# AY_Soundcard.net
KiCad netlist of a schematic drawn in EAGLE
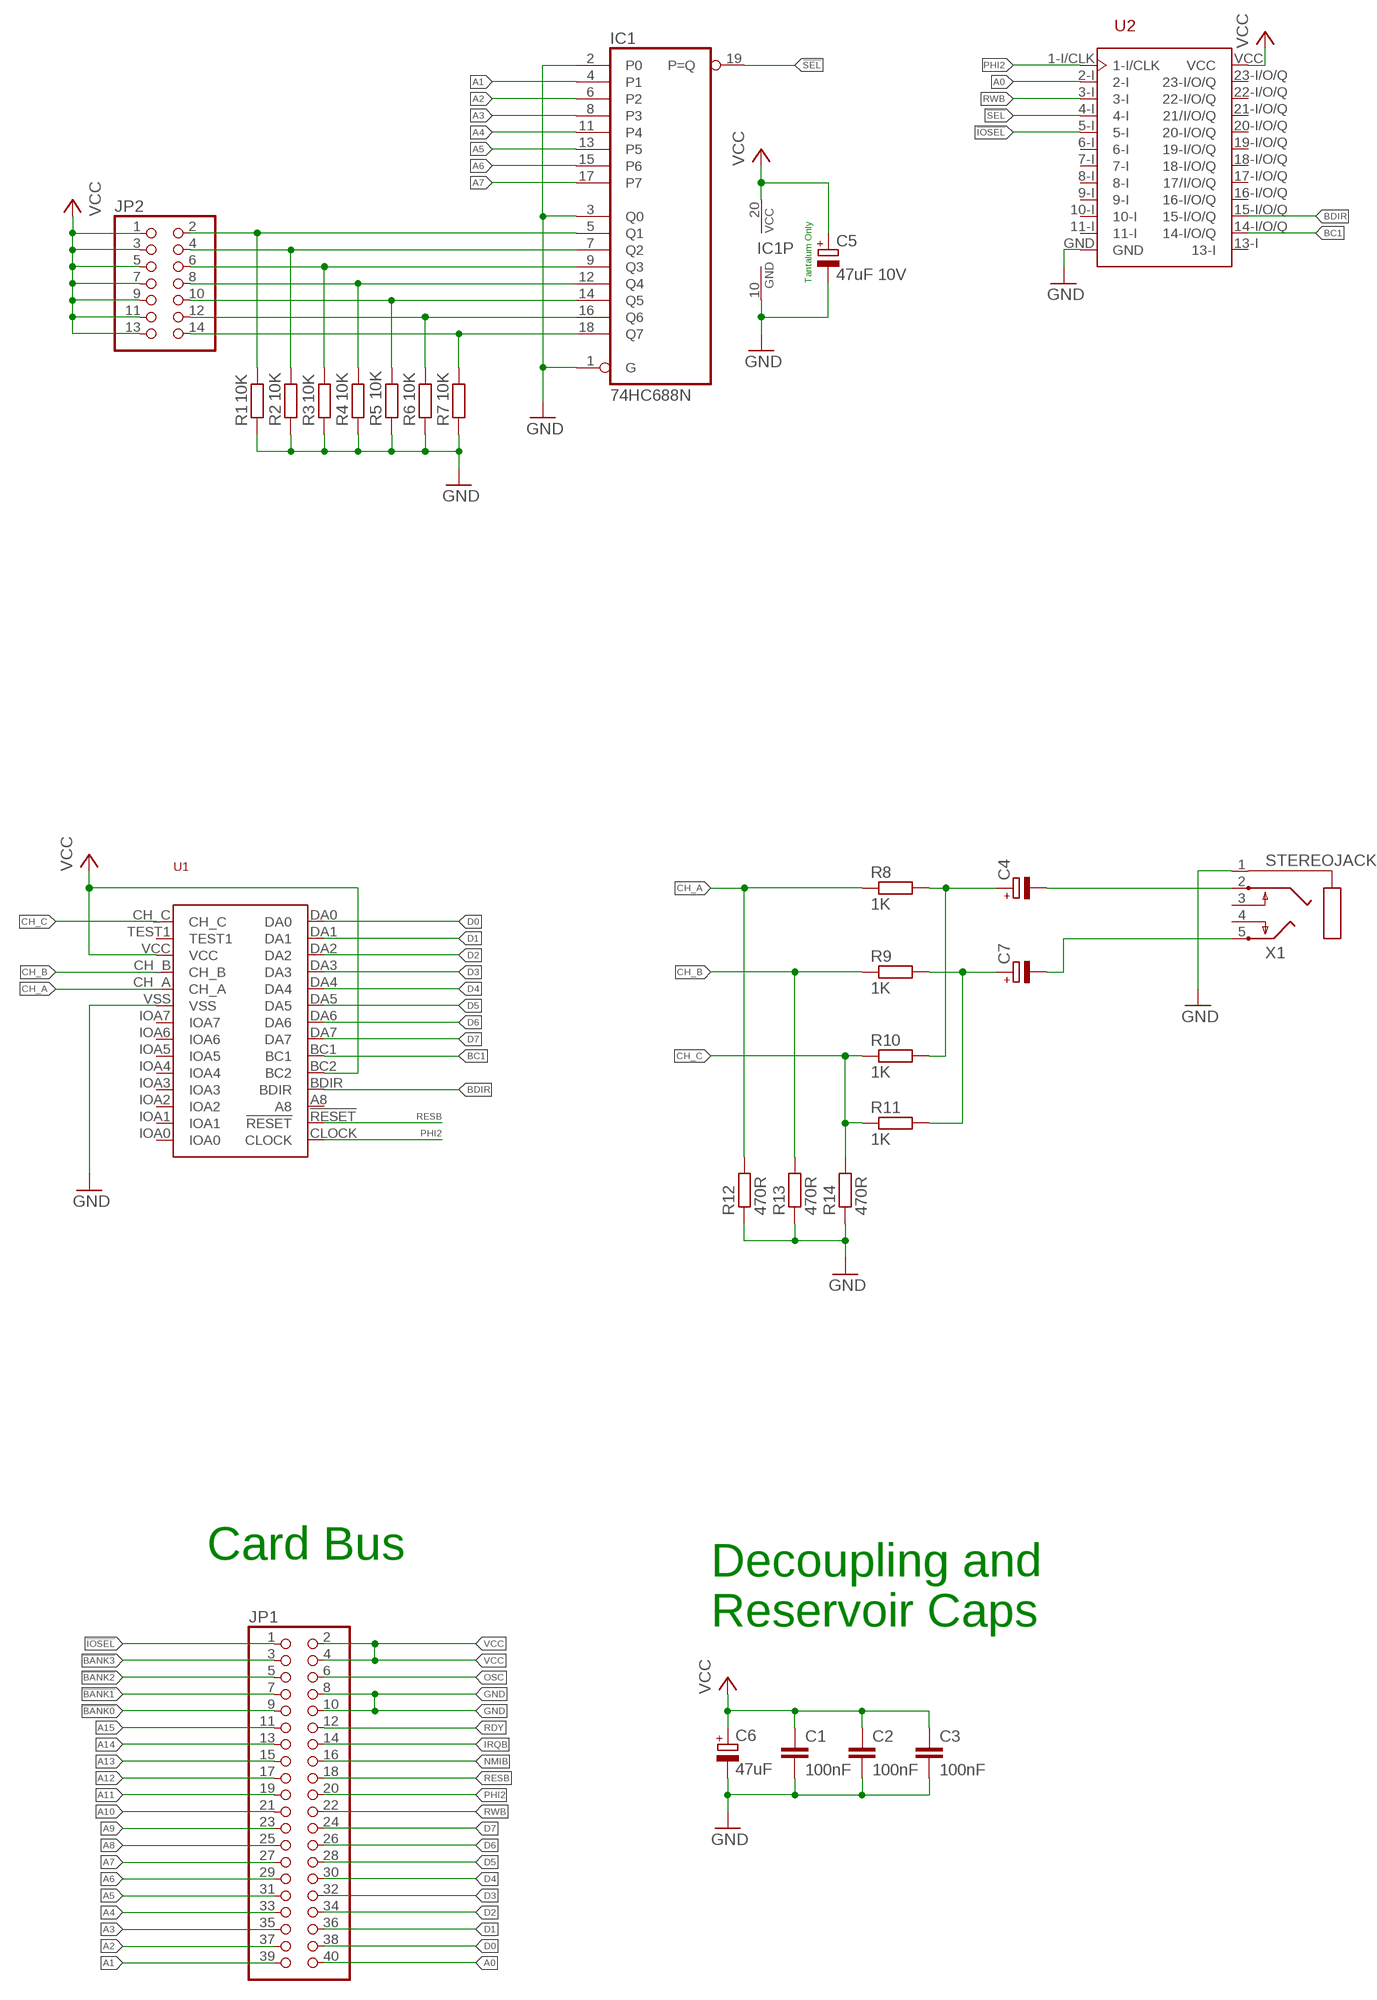
[diagram p0: schematic, sheet 1]

(export (version "E")
  (design (tool "Eeschema 10.0.6"))
  (components
    (comp (ref "C1")
      (value "100nF")
      (footprint "eagle-import:C050-025X075")
      (libsource (lib "eagle-import") (part "C-EU050-025X075"))
    )
    (comp (ref "C2")
      (value "100nF")
      (footprint "eagle-import:C050-025X075")
      (libsource (lib "eagle-import") (part "C-EU050-025X075"))
    )
    (comp (ref "C3")
      (value "100nF")
      (footprint "eagle-import:C050-025X075")
      (libsource (lib "eagle-import") (part "C-EU050-025X075"))
    )
    (comp (ref "C4")
      (value "CPOL-EUE2-5")
      (footprint "eagle-import:E2-5")
      (libsource (lib "eagle-import") (part "CPOL-EUE2-5"))
    )
    (comp (ref "C5")
      (value "47uF 10V")
      (footprint "eagle-import:E5-6")
      (libsource (lib "eagle-import") (part "CPOL-EUE5-6"))
    )
    (comp (ref "C6")
      (value "47uF")
      (footprint "eagle-import:E2,5-7")
      (libsource (lib "eagle-import") (part "CPOL-EUE2.5-7"))
    )
    (comp (ref "C7")
      (value "CPOL-EUE2-5")
      (footprint "eagle-import:E2-5")
      (libsource (lib "eagle-import") (part "CPOL-EUE2-5"))
    )
    (comp (ref "IC1")
      (value "74HC688N")
      (footprint "eagle-import:DIL20")
      (libsource (lib "eagle-import") (part "74688NHC"))
    )
    (comp (ref "JP1")
      (value "PINHD-2X20/90")
      (footprint "eagle-import:2X20_90")
      (libsource (lib "eagle-import") (part "PINHD-2X20/90"))
    )
    (comp (ref "JP2")
      (value "PINHD-2X7")
      (footprint "eagle-import:2X07")
      (libsource (lib "eagle-import") (part "PINHD-2X7"))
    )
    (comp (ref "R1")
      (value "10K")
      (footprint "eagle-import:0207_2V")
      (libsource (lib "eagle-import") (part "R-EU_0207/2V"))
    )
    (comp (ref "R2")
      (value "10K")
      (footprint "eagle-import:0207_2V")
      (libsource (lib "eagle-import") (part "R-EU_0207/2V"))
    )
    (comp (ref "R3")
      (value "10K")
      (footprint "eagle-import:0207_2V")
      (libsource (lib "eagle-import") (part "R-EU_0207/2V"))
    )
    (comp (ref "R4")
      (value "10K")
      (footprint "eagle-import:0207_2V")
      (libsource (lib "eagle-import") (part "R-EU_0207/2V"))
    )
    (comp (ref "R5")
      (value "10K")
      (footprint "eagle-import:0207_2V")
      (libsource (lib "eagle-import") (part "R-EU_0207/2V"))
    )
    (comp (ref "R6")
      (value "10K")
      (footprint "eagle-import:0207_2V")
      (libsource (lib "eagle-import") (part "R-EU_0207/2V"))
    )
    (comp (ref "R7")
      (value "10K")
      (footprint "eagle-import:0207_2V")
      (libsource (lib "eagle-import") (part "R-EU_0207/2V"))
    )
    (comp (ref "R8")
      (value "1K")
      (footprint "eagle-import:0207_2V")
      (libsource (lib "eagle-import") (part "R-EU_0207/2V"))
    )
    (comp (ref "R9")
      (value "1K")
      (footprint "eagle-import:0207_2V")
      (libsource (lib "eagle-import") (part "R-EU_0207/2V"))
    )
    (comp (ref "R10")
      (value "1K")
      (footprint "eagle-import:0207_2V")
      (libsource (lib "eagle-import") (part "R-EU_0207/2V"))
    )
    (comp (ref "R11")
      (value "1K")
      (footprint "eagle-import:0207_2V")
      (libsource (lib "eagle-import") (part "R-EU_0207/2V"))
    )
    (comp (ref "R12")
      (value "470R")
      (footprint "eagle-import:0207_2V")
      (libsource (lib "eagle-import") (part "R-EU_0207/2V"))
    )
    (comp (ref "R13")
      (value "470R")
      (footprint "eagle-import:0207_10")
      (libsource (lib "eagle-import") (part "R-EU_0207/10"))
    )
    (comp (ref "R14")
      (value "470R")
      (footprint "eagle-import:0207_10")
      (libsource (lib "eagle-import") (part "R-EU_0207/10"))
    )
    (comp (ref "U1")
      (value "AY-3-8912-DIP")
      (footprint "eagle-import:DIP")
      (libsource (lib "eagle-import") (part "AY-3-8912-DIP"))
    )
    (comp (ref "U2")
      (value "GAL22V10D-DIP")
      (footprint "eagle-import:DIP24")
      (libsource (lib "eagle-import") (part "GAL22V10D-DIP"))
    )
    (comp (ref "X1")
      (value "STEREOJACK")
      (footprint "eagle-import:STX3100")
      (libsource (lib "eagle-import") (part "STEREOJACK"))
    )
  )
  (nets
    (net (code "1") (name "/~{BANK0}") (class "Default")
      (node (ref "JP1") (pin "9") (pinfunction "9_9") (pintype "passive"))
    )
    (net (code "2") (name "/~{BANK1}") (class "Default")
      (node (ref "JP1") (pin "7") (pinfunction "7_7") (pintype "passive"))
    )
    (net (code "3") (name "/~{BANK2}") (class "Default")
      (node (ref "JP1") (pin "5") (pinfunction "5_5") (pintype "passive"))
    )
    (net (code "4") (name "/~{BANK3}") (class "Default")
      (node (ref "JP1") (pin "3") (pinfunction "3_3") (pintype "passive"))
    )
    (net (code "5") (name "/~{IOSEL}") (class "Default")
      (node (ref "JP1") (pin "1") (pinfunction "1_1") (pintype "passive"))
      (node (ref "U2") (pin "5-I") (pinfunction "5-I_5-I") (pintype "input"))
    )
    (net (code "6") (name "/~{SEL}") (class "Default")
      (node (ref "IC1") (pin "19") (pinfunction "P=Q_19") (pintype "output"))
      (node (ref "U2") (pin "4-I") (pinfunction "4-I_4-I") (pintype "input"))
    )
    (net (code "7") (name "A0") (class "Default")
      (node (ref "JP1") (pin "40") (pinfunction "40_40") (pintype "passive"))
      (node (ref "U2") (pin "2-I") (pinfunction "2-I_2-I") (pintype "input"))
    )
    (net (code "8") (name "A1") (class "Default")
      (node (ref "IC1") (pin "4") (pinfunction "P1_4") (pintype "input"))
      (node (ref "JP1") (pin "39") (pinfunction "39_39") (pintype "passive"))
    )
    (net (code "9") (name "A2") (class "Default")
      (node (ref "IC1") (pin "6") (pinfunction "P2_6") (pintype "input"))
      (node (ref "JP1") (pin "37") (pinfunction "37_37") (pintype "passive"))
    )
    (net (code "10") (name "A3") (class "Default")
      (node (ref "IC1") (pin "8") (pinfunction "P3_8") (pintype "input"))
      (node (ref "JP1") (pin "35") (pinfunction "35_35") (pintype "passive"))
    )
    (net (code "11") (name "A4") (class "Default")
      (node (ref "IC1") (pin "11") (pinfunction "P4_11") (pintype "input"))
      (node (ref "JP1") (pin "33") (pinfunction "33_33") (pintype "passive"))
    )
    (net (code "12") (name "A5") (class "Default")
      (node (ref "IC1") (pin "13") (pinfunction "P5_13") (pintype "input"))
      (node (ref "JP1") (pin "31") (pinfunction "31_31") (pintype "passive"))
    )
    (net (code "13") (name "A6") (class "Default")
      (node (ref "IC1") (pin "15") (pinfunction "P6_15") (pintype "input"))
      (node (ref "JP1") (pin "29") (pinfunction "29_29") (pintype "passive"))
    )
    (net (code "14") (name "A7") (class "Default")
      (node (ref "IC1") (pin "17") (pinfunction "P7_17") (pintype "input"))
      (node (ref "JP1") (pin "27") (pinfunction "27_27") (pintype "passive"))
    )
    (net (code "15") (name "A8") (class "Default")
      (node (ref "JP1") (pin "25") (pinfunction "25_25") (pintype "passive"))
    )
    (net (code "16") (name "A9") (class "Default")
      (node (ref "JP1") (pin "23") (pinfunction "23_23") (pintype "passive"))
    )
    (net (code "17") (name "A10") (class "Default")
      (node (ref "JP1") (pin "21") (pinfunction "21_21") (pintype "passive"))
    )
    (net (code "18") (name "A11") (class "Default")
      (node (ref "JP1") (pin "19") (pinfunction "19_19") (pintype "passive"))
    )
    (net (code "19") (name "A12") (class "Default")
      (node (ref "JP1") (pin "17") (pinfunction "17_17") (pintype "passive"))
    )
    (net (code "20") (name "A13") (class "Default")
      (node (ref "JP1") (pin "15") (pinfunction "15_15") (pintype "passive"))
    )
    (net (code "21") (name "A14") (class "Default")
      (node (ref "JP1") (pin "13") (pinfunction "13_13") (pintype "passive"))
    )
    (net (code "22") (name "A15") (class "Default")
      (node (ref "JP1") (pin "11") (pinfunction "11_11") (pintype "passive"))
    )
    (net (code "23") (name "BC1") (class "Default")
      (node (ref "U1") (pin "BC1") (pinfunction "BC1_BC1") (pintype "input"))
      (node (ref "U2") (pin "14-I/O/Q") (pinfunction "14-I/O/Q_14-I/O/Q") (pintype "bidirectional"))
    )
    (net (code "24") (name "BDIR") (class "Default")
      (node (ref "U1") (pin "BDIR") (pinfunction "BDIR_BDIR") (pintype "input"))
      (node (ref "U2") (pin "15-I/O/Q") (pinfunction "15-I/O/Q_15-I/O/Q") (pintype "bidirectional"))
    )
    (net (code "25") (name "CH_A") (class "Default")
      (node (ref "R12") (pin "2") (pinfunction "2_2") (pintype "passive"))
      (node (ref "R8") (pin "1") (pinfunction "1_1") (pintype "passive"))
      (node (ref "U1") (pin "CH_A") (pinfunction "CH_A_CH_A") (pintype "output"))
    )
    (net (code "26") (name "CH_B") (class "Default")
      (node (ref "R13") (pin "2") (pinfunction "2_2") (pintype "passive"))
      (node (ref "R9") (pin "1") (pinfunction "1_1") (pintype "passive"))
      (node (ref "U1") (pin "CH_B") (pinfunction "CH_B_CH_B") (pintype "output"))
    )
    (net (code "27") (name "CH_C") (class "Default")
      (node (ref "R10") (pin "1") (pinfunction "1_1") (pintype "passive"))
      (node (ref "R11") (pin "1") (pinfunction "1_1") (pintype "passive"))
      (node (ref "R14") (pin "2") (pinfunction "2_2") (pintype "passive"))
      (node (ref "U1") (pin "CH_C") (pinfunction "CH_C_CH_C") (pintype "output"))
    )
    (net (code "28") (name "D0") (class "Default")
      (node (ref "JP1") (pin "38") (pinfunction "38_38") (pintype "passive"))
      (node (ref "U1") (pin "DA0") (pinfunction "DA0_DA0") (pintype "bidirectional"))
    )
    (net (code "29") (name "D1") (class "Default")
      (node (ref "JP1") (pin "36") (pinfunction "36_36") (pintype "passive"))
      (node (ref "U1") (pin "DA1") (pinfunction "DA1_DA1") (pintype "bidirectional"))
    )
    (net (code "30") (name "D2") (class "Default")
      (node (ref "JP1") (pin "34") (pinfunction "34_34") (pintype "passive"))
      (node (ref "U1") (pin "DA2") (pinfunction "DA2_DA2") (pintype "bidirectional"))
    )
    (net (code "31") (name "D3") (class "Default")
      (node (ref "JP1") (pin "32") (pinfunction "32_32") (pintype "passive"))
      (node (ref "U1") (pin "DA3") (pinfunction "DA3_DA3") (pintype "bidirectional"))
    )
    (net (code "32") (name "D4") (class "Default")
      (node (ref "JP1") (pin "30") (pinfunction "30_30") (pintype "passive"))
      (node (ref "U1") (pin "DA4") (pinfunction "DA4_DA4") (pintype "bidirectional"))
    )
    (net (code "33") (name "D5") (class "Default")
      (node (ref "JP1") (pin "28") (pinfunction "28_28") (pintype "passive"))
      (node (ref "U1") (pin "DA5") (pinfunction "DA5_DA5") (pintype "bidirectional"))
    )
    (net (code "34") (name "D6") (class "Default")
      (node (ref "JP1") (pin "26") (pinfunction "26_26") (pintype "passive"))
      (node (ref "U1") (pin "DA6") (pinfunction "DA6_DA6") (pintype "bidirectional"))
    )
    (net (code "35") (name "D7") (class "Default")
      (node (ref "JP1") (pin "24") (pinfunction "24_24") (pintype "passive"))
      (node (ref "U1") (pin "DA7") (pinfunction "DA7_DA7") (pintype "bidirectional"))
    )
    (net (code "36") (name "GND") (class "Default")
      (node (ref "C1") (pin "2") (pinfunction "2_2") (pintype "passive"))
      (node (ref "C2") (pin "2") (pinfunction "2_2") (pintype "passive"))
      (node (ref "C3") (pin "2") (pinfunction "2_2") (pintype "passive"))
      (node (ref "C5") (pin "-") (pinfunction "-_-") (pintype "passive"))
      (node (ref "C6") (pin "-") (pinfunction "-_-") (pintype "passive"))
      (node (ref "IC1") (pin "1") (pinfunction "G_1") (pintype "input"))
      (node (ref "IC1") (pin "10") (pinfunction "GND_10") (pintype "power_in"))
      (node (ref "IC1") (pin "2") (pinfunction "P0_2") (pintype "input"))
      (node (ref "IC1") (pin "3") (pinfunction "Q0_3") (pintype "input"))
      (node (ref "JP1") (pin "10") (pinfunction "10_10") (pintype "passive"))
      (node (ref "JP1") (pin "8") (pinfunction "8_8") (pintype "passive"))
      (node (ref "R1") (pin "1") (pinfunction "1_1") (pintype "passive"))
      (node (ref "R12") (pin "1") (pinfunction "1_1") (pintype "passive"))
      (node (ref "R13") (pin "1") (pinfunction "1_1") (pintype "passive"))
      (node (ref "R14") (pin "1") (pinfunction "1_1") (pintype "passive"))
      (node (ref "R2") (pin "1") (pinfunction "1_1") (pintype "passive"))
      (node (ref "R3") (pin "1") (pinfunction "1_1") (pintype "passive"))
      (node (ref "R4") (pin "1") (pinfunction "1_1") (pintype "passive"))
      (node (ref "R5") (pin "1") (pinfunction "1_1") (pintype "passive"))
      (node (ref "R6") (pin "1") (pinfunction "1_1") (pintype "passive"))
      (node (ref "R7") (pin "1") (pinfunction "1_1") (pintype "passive"))
      (node (ref "U1") (pin "VSS") (pinfunction "VSS_VSS") (pintype "power_in"))
      (node (ref "U2") (pin "GND") (pinfunction "GND_GND") (pintype "power_in"))
      (node (ref "X1") (pin "1") (pinfunction "1_1") (pintype "passive"))
    )
    (net (code "37") (name "IRQB") (class "Default")
      (node (ref "JP1") (pin "14") (pinfunction "14_14") (pintype "passive"))
    )
    (net (code "38") (name "NMIB") (class "Default")
      (node (ref "JP1") (pin "16") (pinfunction "16_16") (pintype "passive"))
    )
    (net (code "39") (name "Net-(C4-Pad+)") (class "Default")
      (node (ref "C4") (pin "+") (pinfunction "+_+") (pintype "passive"))
      (node (ref "R10") (pin "2") (pinfunction "2_2") (pintype "passive"))
      (node (ref "R8") (pin "2") (pinfunction "2_2") (pintype "passive"))
    )
    (net (code "40") (name "Net-(C4-Pad-)") (class "Default")
      (node (ref "C4") (pin "-") (pinfunction "-_-") (pintype "passive"))
      (node (ref "X1") (pin "2") (pinfunction "2_2") (pintype "passive"))
    )
    (net (code "41") (name "Net-(C7-Pad+)") (class "Default")
      (node (ref "C7") (pin "+") (pinfunction "+_+") (pintype "passive"))
      (node (ref "R11") (pin "2") (pinfunction "2_2") (pintype "passive"))
      (node (ref "R9") (pin "2") (pinfunction "2_2") (pintype "passive"))
    )
    (net (code "42") (name "Net-(C7-Pad-)") (class "Default")
      (node (ref "C7") (pin "-") (pinfunction "-_-") (pintype "passive"))
      (node (ref "X1") (pin "5") (pinfunction "5_5") (pintype "passive"))
    )
    (net (code "43") (name "Net-(IC1A-Q1)") (class "Default")
      (node (ref "IC1") (pin "5") (pinfunction "Q1_5") (pintype "input"))
      (node (ref "JP2") (pin "2") (pinfunction "2_2") (pintype "passive"))
      (node (ref "R1") (pin "2") (pinfunction "2_2") (pintype "passive"))
    )
    (net (code "44") (name "Net-(IC1A-Q2)") (class "Default")
      (node (ref "IC1") (pin "7") (pinfunction "Q2_7") (pintype "input"))
      (node (ref "JP2") (pin "4") (pinfunction "4_4") (pintype "passive"))
      (node (ref "R2") (pin "2") (pinfunction "2_2") (pintype "passive"))
    )
    (net (code "45") (name "Net-(IC1A-Q3)") (class "Default")
      (node (ref "IC1") (pin "9") (pinfunction "Q3_9") (pintype "input"))
      (node (ref "JP2") (pin "6") (pinfunction "6_6") (pintype "passive"))
      (node (ref "R3") (pin "2") (pinfunction "2_2") (pintype "passive"))
    )
    (net (code "46") (name "Net-(IC1A-Q4)") (class "Default")
      (node (ref "IC1") (pin "12") (pinfunction "Q4_12") (pintype "input"))
      (node (ref "JP2") (pin "8") (pinfunction "8_8") (pintype "passive"))
      (node (ref "R4") (pin "2") (pinfunction "2_2") (pintype "passive"))
    )
    (net (code "47") (name "Net-(IC1A-Q5)") (class "Default")
      (node (ref "IC1") (pin "14") (pinfunction "Q5_14") (pintype "input"))
      (node (ref "JP2") (pin "10") (pinfunction "10_10") (pintype "passive"))
      (node (ref "R5") (pin "2") (pinfunction "2_2") (pintype "passive"))
    )
    (net (code "48") (name "Net-(IC1A-Q6)") (class "Default")
      (node (ref "IC1") (pin "16") (pinfunction "Q6_16") (pintype "input"))
      (node (ref "JP2") (pin "12") (pinfunction "12_12") (pintype "passive"))
      (node (ref "R6") (pin "2") (pinfunction "2_2") (pintype "passive"))
    )
    (net (code "49") (name "Net-(IC1A-Q7)") (class "Default")
      (node (ref "IC1") (pin "18") (pinfunction "Q7_18") (pintype "input"))
      (node (ref "JP2") (pin "14") (pinfunction "14_14") (pintype "passive"))
      (node (ref "R7") (pin "2") (pinfunction "2_2") (pintype "passive"))
    )
    (net (code "50") (name "OSC") (class "Default")
      (node (ref "JP1") (pin "6") (pinfunction "6_6") (pintype "passive"))
    )
    (net (code "51") (name "PHI2") (class "Default")
      (node (ref "JP1") (pin "20") (pinfunction "20_20") (pintype "passive"))
      (node (ref "U1") (pin "CLOCK") (pinfunction "CLOCK_CLOCK") (pintype "input"))
      (node (ref "U2") (pin "1-I/CLK") (pinfunction "1-I/CLK_1-I/CLK") (pintype "input"))
    )
    (net (code "52") (name "RDY") (class "Default")
      (node (ref "JP1") (pin "12") (pinfunction "12_12") (pintype "passive"))
    )
    (net (code "53") (name "RESB") (class "Default")
      (node (ref "JP1") (pin "18") (pinfunction "18_18") (pintype "passive"))
      (node (ref "U1") (pin "!RESET") (pinfunction "~{RESET}_!RESET") (pintype "input"))
    )
    (net (code "54") (name "RWB") (class "Default")
      (node (ref "JP1") (pin "22") (pinfunction "22_22") (pintype "passive"))
      (node (ref "U2") (pin "3-I") (pinfunction "3-I_3-I") (pintype "input"))
    )
    (net (code "55") (name "VCC") (class "Default")
      (node (ref "C1") (pin "1") (pinfunction "1_1") (pintype "passive"))
      (node (ref "C2") (pin "1") (pinfunction "1_1") (pintype "passive"))
      (node (ref "C3") (pin "1") (pinfunction "1_1") (pintype "passive"))
      (node (ref "C5") (pin "+") (pinfunction "+_+") (pintype "passive"))
      (node (ref "C6") (pin "+") (pinfunction "+_+") (pintype "passive"))
      (node (ref "IC1") (pin "20") (pinfunction "VCC_20") (pintype "power_in"))
      (node (ref "JP1") (pin "2") (pinfunction "2_2") (pintype "passive"))
      (node (ref "JP1") (pin "4") (pinfunction "4_4") (pintype "passive"))
      (node (ref "JP2") (pin "1") (pinfunction "1_1") (pintype "passive"))
      (node (ref "JP2") (pin "11") (pinfunction "11_11") (pintype "passive"))
      (node (ref "JP2") (pin "13") (pinfunction "13_13") (pintype "passive"))
      (node (ref "JP2") (pin "3") (pinfunction "3_3") (pintype "passive"))
      (node (ref "JP2") (pin "5") (pinfunction "5_5") (pintype "passive"))
      (node (ref "JP2") (pin "7") (pinfunction "7_7") (pintype "passive"))
      (node (ref "JP2") (pin "9") (pinfunction "9_9") (pintype "passive"))
      (node (ref "U1") (pin "BC2") (pinfunction "BC2_BC2") (pintype "input"))
      (node (ref "U1") (pin "VCC") (pinfunction "VCC_VCC") (pintype "power_in"))
      (node (ref "U2") (pin "VCC") (pinfunction "VCC_VCC") (pintype "power_in"))
    )
    (net (code "56") (name "unconnected-(U1-PadA8)") (class "Default")
      (node (ref "U1") (pin "A8") (pinfunction "A8_A8") (pintype "input"))
    )
    (net (code "57") (name "unconnected-(U1-PadIOA0)") (class "Default")
      (node (ref "U1") (pin "IOA0") (pinfunction "IOA0_IOA0") (pintype "bidirectional"))
    )
    (net (code "58") (name "unconnected-(U1-PadIOA1)") (class "Default")
      (node (ref "U1") (pin "IOA1") (pinfunction "IOA1_IOA1") (pintype "bidirectional"))
    )
    (net (code "59") (name "unconnected-(U1-PadIOA2)") (class "Default")
      (node (ref "U1") (pin "IOA2") (pinfunction "IOA2_IOA2") (pintype "bidirectional"))
    )
    (net (code "60") (name "unconnected-(U1-PadIOA3)") (class "Default")
      (node (ref "U1") (pin "IOA3") (pinfunction "IOA3_IOA3") (pintype "bidirectional"))
    )
    (net (code "61") (name "unconnected-(U1-PadIOA4)") (class "Default")
      (node (ref "U1") (pin "IOA4") (pinfunction "IOA4_IOA4") (pintype "bidirectional"))
    )
    (net (code "62") (name "unconnected-(U1-PadIOA5)") (class "Default")
      (node (ref "U1") (pin "IOA5") (pinfunction "IOA5_IOA5") (pintype "bidirectional"))
    )
    (net (code "63") (name "unconnected-(U1-PadIOA6)") (class "Default")
      (node (ref "U1") (pin "IOA6") (pinfunction "IOA6_IOA6") (pintype "bidirectional"))
    )
    (net (code "64") (name "unconnected-(U1-PadIOA7)") (class "Default")
      (node (ref "U1") (pin "IOA7") (pinfunction "IOA7_IOA7") (pintype "bidirectional"))
    )
    (net (code "65") (name "unconnected-(U1-PadTEST1)") (class "Default")
      (node (ref "U1") (pin "TEST1") (pinfunction "TEST1_TEST1") (pintype "no_connect"))
    )
    (net (code "66") (name "unconnected-(U2-17{slash}I{slash}O{slash}Q-Pad17-I{slash}O{slash}Q)") (class "Default")
      (node (ref "U2") (pin "17-I/O/Q") (pinfunction "17/I/O/Q_17-I/O/Q") (pintype "bidirectional"))
    )
    (net (code "67") (name "unconnected-(U2-21{slash}I{slash}O{slash}Q-Pad21-I{slash}O{slash}Q)") (class "Default")
      (node (ref "U2") (pin "21-I/O/Q") (pinfunction "21/I/O/Q_21-I/O/Q") (pintype "bidirectional"))
    )
    (net (code "68") (name "unconnected-(U2-Pad6-I)") (class "Default")
      (node (ref "U2") (pin "6-I") (pinfunction "6-I_6-I") (pintype "input"))
    )
    (net (code "69") (name "unconnected-(U2-Pad7-I)") (class "Default")
      (node (ref "U2") (pin "7-I") (pinfunction "7-I_7-I") (pintype "input"))
    )
    (net (code "70") (name "unconnected-(U2-Pad8-I)") (class "Default")
      (node (ref "U2") (pin "8-I") (pinfunction "8-I_8-I") (pintype "input"))
    )
    (net (code "71") (name "unconnected-(U2-Pad9-I)") (class "Default")
      (node (ref "U2") (pin "9-I") (pinfunction "9-I_9-I") (pintype "input"))
    )
    (net (code "72") (name "unconnected-(U2-Pad10-I)") (class "Default")
      (node (ref "U2") (pin "10-I") (pinfunction "10-I_10-I") (pintype "input"))
    )
    (net (code "73") (name "unconnected-(U2-Pad11-I)") (class "Default")
      (node (ref "U2") (pin "11-I") (pinfunction "11-I_11-I") (pintype "input"))
    )
    (net (code "74") (name "unconnected-(U2-Pad13-I)") (class "Default")
      (node (ref "U2") (pin "13-I") (pinfunction "13-I_13-I") (pintype "input"))
    )
    (net (code "75") (name "unconnected-(U2-Pad16-I{slash}O{slash}Q)") (class "Default")
      (node (ref "U2") (pin "16-I/O/Q") (pinfunction "16-I/O/Q_16-I/O/Q") (pintype "bidirectional"))
    )
    (net (code "76") (name "unconnected-(U2-Pad18-I{slash}O{slash}Q)") (class "Default")
      (node (ref "U2") (pin "18-I/O/Q") (pinfunction "18-I/O/Q_18-I/O/Q") (pintype "bidirectional"))
    )
    (net (code "77") (name "unconnected-(U2-Pad19-I{slash}O{slash}Q)") (class "Default")
      (node (ref "U2") (pin "19-I/O/Q") (pinfunction "19-I/O/Q_19-I/O/Q") (pintype "bidirectional"))
    )
    (net (code "78") (name "unconnected-(U2-Pad20-I{slash}O{slash}Q)") (class "Default")
      (node (ref "U2") (pin "20-I/O/Q") (pinfunction "20-I/O/Q_20-I/O/Q") (pintype "bidirectional"))
    )
    (net (code "79") (name "unconnected-(U2-Pad22-I{slash}O{slash}Q)") (class "Default")
      (node (ref "U2") (pin "22-I/O/Q") (pinfunction "22-I/O/Q_22-I/O/Q") (pintype "bidirectional"))
    )
    (net (code "80") (name "unconnected-(U2-Pad23-I{slash}O{slash}Q)") (class "Default")
      (node (ref "U2") (pin "23-I/O/Q") (pinfunction "23-I/O/Q_23-I/O/Q") (pintype "bidirectional"))
    )
    (net (code "81") (name "unconnected-(X1-Pad3)") (class "Default")
      (node (ref "X1") (pin "3") (pinfunction "3_3") (pintype "passive"))
    )
    (net (code "82") (name "unconnected-(X1-Pad4)") (class "Default")
      (node (ref "X1") (pin "4") (pinfunction "4_4") (pintype "passive"))
    )
  )
)
